# rel-regs.net
KiCad netlist of a schematic drawn in EAGLE
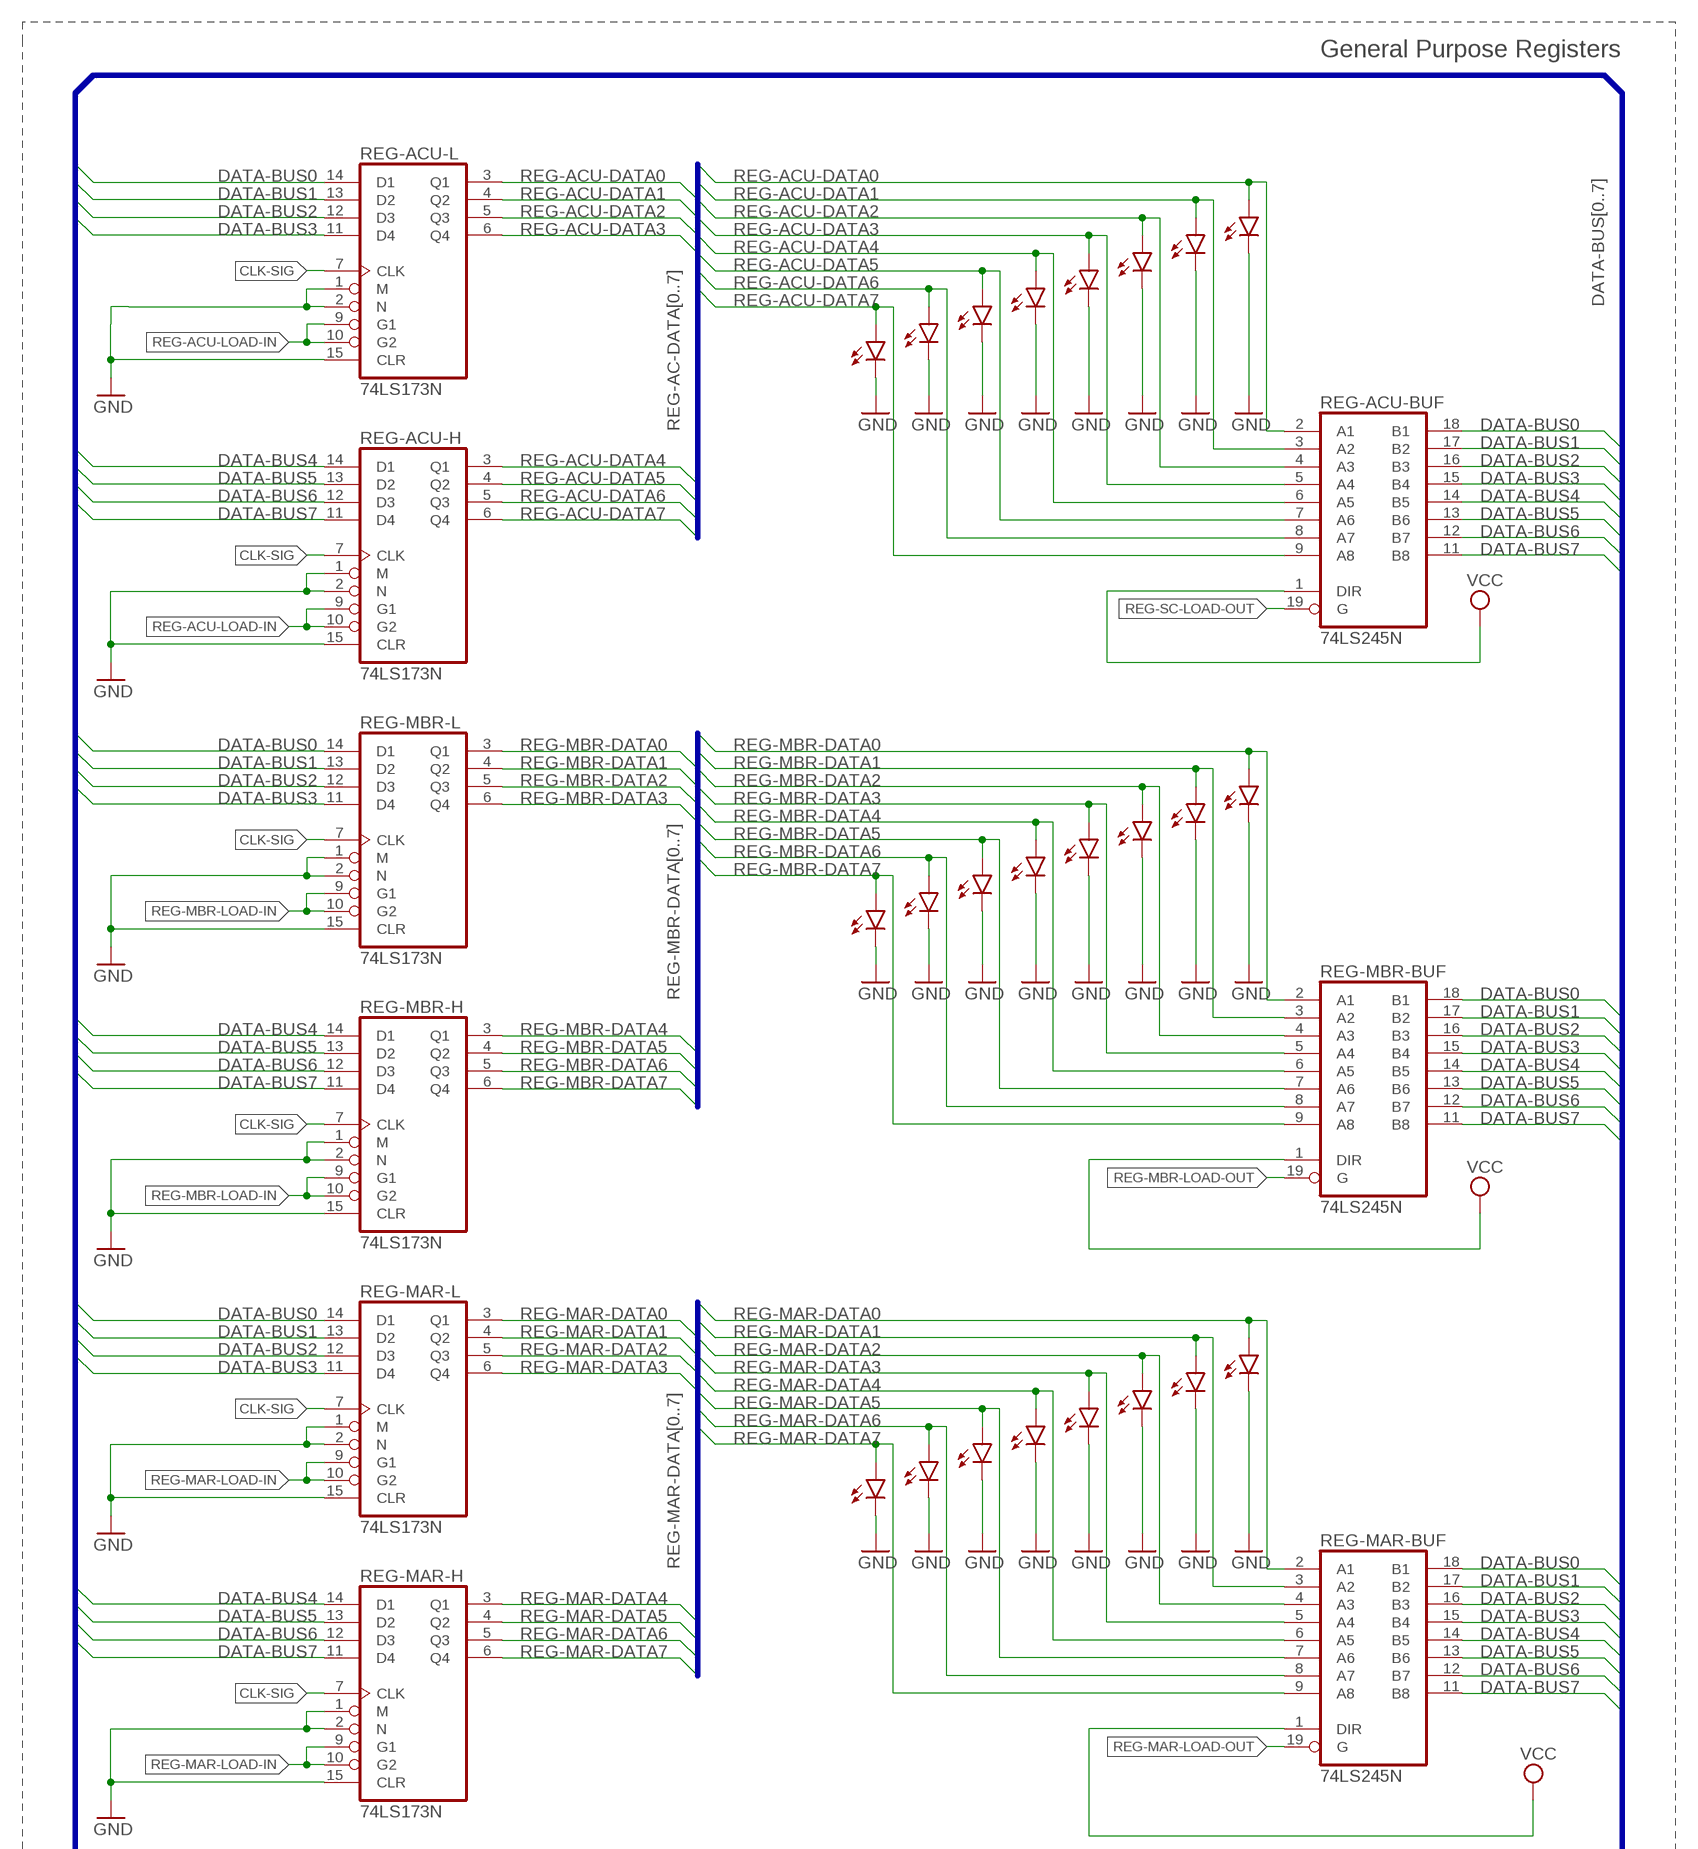
[diagram p0: schematic, sheet 1, part 1 of 2]
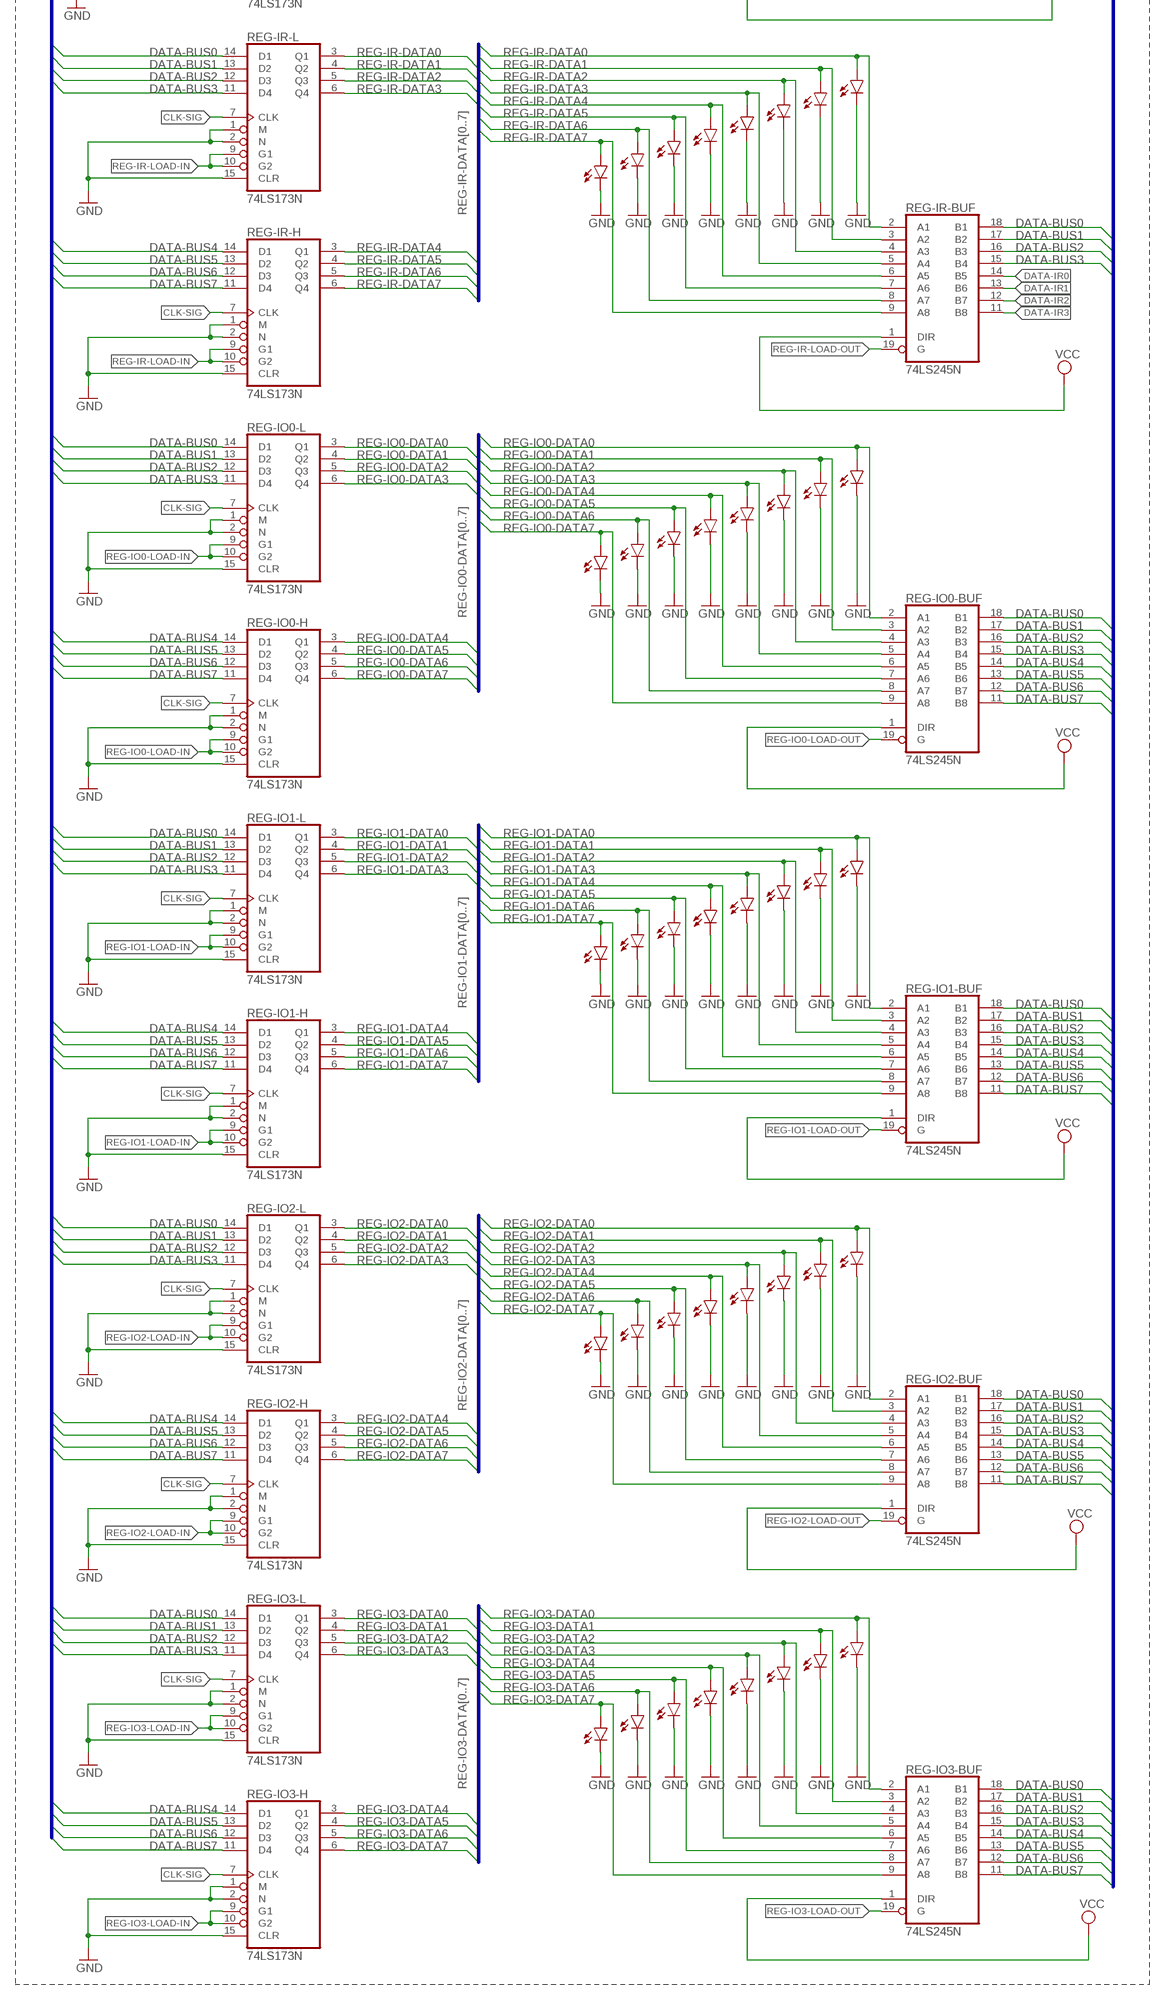
[diagram p1: schematic, sheet 1, part 2 of 2]

(export (version "E")
  (design (tool "Eeschema 10.0.6"))
  (components
    (comp (ref "LED0")
      (value "LED5MM")
      (footprint "eagle-import:LED5MM")
      (libsource (lib "eagle-import") (part "LED5MM"))
    )
    (comp (ref "LED1")
      (value "LED5MM")
      (footprint "eagle-import:LED5MM")
      (libsource (lib "eagle-import") (part "LED5MM"))
    )
    (comp (ref "LED2")
      (value "LED5MM")
      (footprint "eagle-import:LED5MM")
      (libsource (lib "eagle-import") (part "LED5MM"))
    )
    (comp (ref "LED3")
      (value "LED5MM")
      (footprint "eagle-import:LED5MM")
      (libsource (lib "eagle-import") (part "LED5MM"))
    )
    (comp (ref "LED4")
      (value "LED5MM")
      (footprint "eagle-import:LED5MM")
      (libsource (lib "eagle-import") (part "LED5MM"))
    )
    (comp (ref "LED5")
      (value "LED5MM")
      (footprint "eagle-import:LED5MM")
      (libsource (lib "eagle-import") (part "LED5MM"))
    )
    (comp (ref "LED6")
      (value "LED5MM")
      (footprint "eagle-import:LED5MM")
      (libsource (lib "eagle-import") (part "LED5MM"))
    )
    (comp (ref "LED7")
      (value "LED5MM")
      (footprint "eagle-import:LED5MM")
      (libsource (lib "eagle-import") (part "LED5MM"))
    )
    (comp (ref "LED8")
      (value "LED5MM")
      (footprint "eagle-import:LED5MM")
      (libsource (lib "eagle-import") (part "LED5MM"))
    )
    (comp (ref "LED9")
      (value "LED5MM")
      (footprint "eagle-import:LED5MM")
      (libsource (lib "eagle-import") (part "LED5MM"))
    )
    (comp (ref "LED10")
      (value "LED5MM")
      (footprint "eagle-import:LED5MM")
      (libsource (lib "eagle-import") (part "LED5MM"))
    )
    (comp (ref "LED11")
      (value "LED5MM")
      (footprint "eagle-import:LED5MM")
      (libsource (lib "eagle-import") (part "LED5MM"))
    )
    (comp (ref "LED12")
      (value "LED5MM")
      (footprint "eagle-import:LED5MM")
      (libsource (lib "eagle-import") (part "LED5MM"))
    )
    (comp (ref "LED13")
      (value "LED5MM")
      (footprint "eagle-import:LED5MM")
      (libsource (lib "eagle-import") (part "LED5MM"))
    )
    (comp (ref "LED14")
      (value "LED5MM")
      (footprint "eagle-import:LED5MM")
      (libsource (lib "eagle-import") (part "LED5MM"))
    )
    (comp (ref "LED15")
      (value "LED5MM")
      (footprint "eagle-import:LED5MM")
      (libsource (lib "eagle-import") (part "LED5MM"))
    )
    (comp (ref "LED16")
      (value "LED5MM")
      (footprint "eagle-import:LED5MM")
      (libsource (lib "eagle-import") (part "LED5MM"))
    )
    (comp (ref "LED17")
      (value "LED5MM")
      (footprint "eagle-import:LED5MM")
      (libsource (lib "eagle-import") (part "LED5MM"))
    )
    (comp (ref "LED18")
      (value "LED5MM")
      (footprint "eagle-import:LED5MM")
      (libsource (lib "eagle-import") (part "LED5MM"))
    )
    (comp (ref "LED19")
      (value "LED5MM")
      (footprint "eagle-import:LED5MM")
      (libsource (lib "eagle-import") (part "LED5MM"))
    )
    (comp (ref "LED20")
      (value "LED5MM")
      (footprint "eagle-import:LED5MM")
      (libsource (lib "eagle-import") (part "LED5MM"))
    )
    (comp (ref "LED21")
      (value "LED5MM")
      (footprint "eagle-import:LED5MM")
      (libsource (lib "eagle-import") (part "LED5MM"))
    )
    (comp (ref "LED22")
      (value "LED5MM")
      (footprint "eagle-import:LED5MM")
      (libsource (lib "eagle-import") (part "LED5MM"))
    )
    (comp (ref "LED23")
      (value "LED5MM")
      (footprint "eagle-import:LED5MM")
      (libsource (lib "eagle-import") (part "LED5MM"))
    )
    (comp (ref "LED24")
      (value "LED5MM")
      (footprint "eagle-import:LED5MM")
      (libsource (lib "eagle-import") (part "LED5MM"))
    )
    (comp (ref "LED25")
      (value "LED5MM")
      (footprint "eagle-import:LED5MM")
      (libsource (lib "eagle-import") (part "LED5MM"))
    )
    (comp (ref "LED26")
      (value "LED5MM")
      (footprint "eagle-import:LED5MM")
      (libsource (lib "eagle-import") (part "LED5MM"))
    )
    (comp (ref "LED27")
      (value "LED5MM")
      (footprint "eagle-import:LED5MM")
      (libsource (lib "eagle-import") (part "LED5MM"))
    )
    (comp (ref "LED28")
      (value "LED5MM")
      (footprint "eagle-import:LED5MM")
      (libsource (lib "eagle-import") (part "LED5MM"))
    )
    (comp (ref "LED29")
      (value "LED5MM")
      (footprint "eagle-import:LED5MM")
      (libsource (lib "eagle-import") (part "LED5MM"))
    )
    (comp (ref "LED30")
      (value "LED5MM")
      (footprint "eagle-import:LED5MM")
      (libsource (lib "eagle-import") (part "LED5MM"))
    )
    (comp (ref "LED31")
      (value "LED5MM")
      (footprint "eagle-import:LED5MM")
      (libsource (lib "eagle-import") (part "LED5MM"))
    )
    (comp (ref "LED32")
      (value "LED5MM")
      (footprint "eagle-import:LED5MM")
      (libsource (lib "eagle-import") (part "LED5MM"))
    )
    (comp (ref "LED33")
      (value "LED5MM")
      (footprint "eagle-import:LED5MM")
      (libsource (lib "eagle-import") (part "LED5MM"))
    )
    (comp (ref "LED34")
      (value "LED5MM")
      (footprint "eagle-import:LED5MM")
      (libsource (lib "eagle-import") (part "LED5MM"))
    )
    (comp (ref "LED35")
      (value "LED5MM")
      (footprint "eagle-import:LED5MM")
      (libsource (lib "eagle-import") (part "LED5MM"))
    )
    (comp (ref "LED36")
      (value "LED5MM")
      (footprint "eagle-import:LED5MM")
      (libsource (lib "eagle-import") (part "LED5MM"))
    )
    (comp (ref "LED37")
      (value "LED5MM")
      (footprint "eagle-import:LED5MM")
      (libsource (lib "eagle-import") (part "LED5MM"))
    )
    (comp (ref "LED38")
      (value "LED5MM")
      (footprint "eagle-import:LED5MM")
      (libsource (lib "eagle-import") (part "LED5MM"))
    )
    (comp (ref "LED39")
      (value "LED5MM")
      (footprint "eagle-import:LED5MM")
      (libsource (lib "eagle-import") (part "LED5MM"))
    )
    (comp (ref "LED40")
      (value "LED5MM")
      (footprint "eagle-import:LED5MM")
      (libsource (lib "eagle-import") (part "LED5MM"))
    )
    (comp (ref "LED41")
      (value "LED5MM")
      (footprint "eagle-import:LED5MM")
      (libsource (lib "eagle-import") (part "LED5MM"))
    )
    (comp (ref "LED42")
      (value "LED5MM")
      (footprint "eagle-import:LED5MM")
      (libsource (lib "eagle-import") (part "LED5MM"))
    )
    (comp (ref "LED43")
      (value "LED5MM")
      (footprint "eagle-import:LED5MM")
      (libsource (lib "eagle-import") (part "LED5MM"))
    )
    (comp (ref "LED44")
      (value "LED5MM")
      (footprint "eagle-import:LED5MM")
      (libsource (lib "eagle-import") (part "LED5MM"))
    )
    (comp (ref "LED45")
      (value "LED5MM")
      (footprint "eagle-import:LED5MM")
      (libsource (lib "eagle-import") (part "LED5MM"))
    )
    (comp (ref "LED46")
      (value "LED5MM")
      (footprint "eagle-import:LED5MM")
      (libsource (lib "eagle-import") (part "LED5MM"))
    )
    (comp (ref "LED47")
      (value "LED5MM")
      (footprint "eagle-import:LED5MM")
      (libsource (lib "eagle-import") (part "LED5MM"))
    )
    (comp (ref "LED48")
      (value "LED5MM")
      (footprint "eagle-import:LED5MM")
      (libsource (lib "eagle-import") (part "LED5MM"))
    )
    (comp (ref "LED49")
      (value "LED5MM")
      (footprint "eagle-import:LED5MM")
      (libsource (lib "eagle-import") (part "LED5MM"))
    )
    (comp (ref "LED50")
      (value "LED5MM")
      (footprint "eagle-import:LED5MM")
      (libsource (lib "eagle-import") (part "LED5MM"))
    )
    (comp (ref "LED51")
      (value "LED5MM")
      (footprint "eagle-import:LED5MM")
      (libsource (lib "eagle-import") (part "LED5MM"))
    )
    (comp (ref "LED52")
      (value "LED5MM")
      (footprint "eagle-import:LED5MM")
      (libsource (lib "eagle-import") (part "LED5MM"))
    )
    (comp (ref "LED53")
      (value "LED5MM")
      (footprint "eagle-import:LED5MM")
      (libsource (lib "eagle-import") (part "LED5MM"))
    )
    (comp (ref "LED54")
      (value "LED5MM")
      (footprint "eagle-import:LED5MM")
      (libsource (lib "eagle-import") (part "LED5MM"))
    )
    (comp (ref "LED55")
      (value "LED5MM")
      (footprint "eagle-import:LED5MM")
      (libsource (lib "eagle-import") (part "LED5MM"))
    )
    (comp (ref "LED56")
      (value "LED5MM")
      (footprint "eagle-import:LED5MM")
      (libsource (lib "eagle-import") (part "LED5MM"))
    )
    (comp (ref "LED57")
      (value "LED5MM")
      (footprint "eagle-import:LED5MM")
      (libsource (lib "eagle-import") (part "LED5MM"))
    )
    (comp (ref "LED58")
      (value "LED5MM")
      (footprint "eagle-import:LED5MM")
      (libsource (lib "eagle-import") (part "LED5MM"))
    )
    (comp (ref "LED59")
      (value "LED5MM")
      (footprint "eagle-import:LED5MM")
      (libsource (lib "eagle-import") (part "LED5MM"))
    )
    (comp (ref "LED60")
      (value "LED5MM")
      (footprint "eagle-import:LED5MM")
      (libsource (lib "eagle-import") (part "LED5MM"))
    )
    (comp (ref "LED61")
      (value "LED5MM")
      (footprint "eagle-import:LED5MM")
      (libsource (lib "eagle-import") (part "LED5MM"))
    )
    (comp (ref "LED62")
      (value "LED5MM")
      (footprint "eagle-import:LED5MM")
      (libsource (lib "eagle-import") (part "LED5MM"))
    )
    (comp (ref "LED63")
      (value "LED5MM")
      (footprint "eagle-import:LED5MM")
      (libsource (lib "eagle-import") (part "LED5MM"))
    )
    (comp (ref "REG-ACU-BUF")
      (value "74LS245N")
      (footprint "eagle-import:DIL20")
      (libsource (lib "eagle-import") (part "74245NLS"))
    )
    (comp (ref "REG-ACU-H")
      (value "74LS173N")
      (footprint "eagle-import:DIL16")
      (libsource (lib "eagle-import") (part "74173NLS"))
    )
    (comp (ref "REG-ACU-L")
      (value "74LS173N")
      (footprint "eagle-import:DIL16")
      (libsource (lib "eagle-import") (part "74173NLS"))
    )
    (comp (ref "REG-IO0-BUF")
      (value "74LS245N")
      (footprint "eagle-import:DIL20")
      (libsource (lib "eagle-import") (part "74245NLS"))
    )
    (comp (ref "REG-IO0-H")
      (value "74LS173N")
      (footprint "eagle-import:DIL16")
      (libsource (lib "eagle-import") (part "74173NLS"))
    )
    (comp (ref "REG-IO0-L")
      (value "74LS173N")
      (footprint "eagle-import:DIL16")
      (libsource (lib "eagle-import") (part "74173NLS"))
    )
    (comp (ref "REG-IO1-BUF")
      (value "74LS245N")
      (footprint "eagle-import:DIL20")
      (libsource (lib "eagle-import") (part "74245NLS"))
    )
    (comp (ref "REG-IO1-H")
      (value "74LS173N")
      (footprint "eagle-import:DIL16")
      (libsource (lib "eagle-import") (part "74173NLS"))
    )
    (comp (ref "REG-IO1-L")
      (value "74LS173N")
      (footprint "eagle-import:DIL16")
      (libsource (lib "eagle-import") (part "74173NLS"))
    )
    (comp (ref "REG-IO2-BUF")
      (value "74LS245N")
      (footprint "eagle-import:DIL20")
      (libsource (lib "eagle-import") (part "74245NLS"))
    )
    (comp (ref "REG-IO2-H")
      (value "74LS173N")
      (footprint "eagle-import:DIL16")
      (libsource (lib "eagle-import") (part "74173NLS"))
    )
    (comp (ref "REG-IO2-L")
      (value "74LS173N")
      (footprint "eagle-import:DIL16")
      (libsource (lib "eagle-import") (part "74173NLS"))
    )
    (comp (ref "REG-IO3-BUF")
      (value "74LS245N")
      (footprint "eagle-import:DIL20")
      (libsource (lib "eagle-import") (part "74245NLS"))
    )
    (comp (ref "REG-IO3-H")
      (value "74LS173N")
      (footprint "eagle-import:DIL16")
      (libsource (lib "eagle-import") (part "74173NLS"))
    )
    (comp (ref "REG-IO3-L")
      (value "74LS173N")
      (footprint "eagle-import:DIL16")
      (libsource (lib "eagle-import") (part "74173NLS"))
    )
    (comp (ref "REG-IR-BUF")
      (value "74LS245N")
      (footprint "eagle-import:DIL20")
      (libsource (lib "eagle-import") (part "74245NLS"))
    )
    (comp (ref "REG-IR-H")
      (value "74LS173N")
      (footprint "eagle-import:DIL16")
      (libsource (lib "eagle-import") (part "74173NLS"))
    )
    (comp (ref "REG-IR-L")
      (value "74LS173N")
      (footprint "eagle-import:DIL16")
      (libsource (lib "eagle-import") (part "74173NLS"))
    )
    (comp (ref "REG-MAR-BUF")
      (value "74LS245N")
      (footprint "eagle-import:DIL20")
      (libsource (lib "eagle-import") (part "74245NLS"))
    )
    (comp (ref "REG-MAR-H")
      (value "74LS173N")
      (footprint "eagle-import:DIL16")
      (libsource (lib "eagle-import") (part "74173NLS"))
    )
    (comp (ref "REG-MAR-L")
      (value "74LS173N")
      (footprint "eagle-import:DIL16")
      (libsource (lib "eagle-import") (part "74173NLS"))
    )
    (comp (ref "REG-MBR-BUF")
      (value "74LS245N")
      (footprint "eagle-import:DIL20")
      (libsource (lib "eagle-import") (part "74245NLS"))
    )
    (comp (ref "REG-MBR-H")
      (value "74LS173N")
      (footprint "eagle-import:DIL16")
      (libsource (lib "eagle-import") (part "74173NLS"))
    )
    (comp (ref "REG-MBR-L")
      (value "74LS173N")
      (footprint "eagle-import:DIL16")
      (libsource (lib "eagle-import") (part "74173NLS"))
    )
  )
  (nets
    (net (code "9") (name "/DATA-BUS0") (class "Default")
      (node (ref "REG-ACU-BUF") (pin "18") (pinfunction "B1_18") (pintype "bidirectional"))
      (node (ref "REG-ACU-L") (pin "14") (pinfunction "D1_14") (pintype "input"))
      (node (ref "REG-IO0-BUF") (pin "18") (pinfunction "B1_18") (pintype "bidirectional"))
      (node (ref "REG-IO0-L") (pin "14") (pinfunction "D1_14") (pintype "input"))
      (node (ref "REG-IO1-BUF") (pin "18") (pinfunction "B1_18") (pintype "bidirectional"))
      (node (ref "REG-IO1-L") (pin "14") (pinfunction "D1_14") (pintype "input"))
      (node (ref "REG-IO2-BUF") (pin "18") (pinfunction "B1_18") (pintype "bidirectional"))
      (node (ref "REG-IO2-L") (pin "14") (pinfunction "D1_14") (pintype "input"))
      (node (ref "REG-IO3-BUF") (pin "18") (pinfunction "B1_18") (pintype "bidirectional"))
      (node (ref "REG-IO3-L") (pin "14") (pinfunction "D1_14") (pintype "input"))
      (node (ref "REG-IR-BUF") (pin "18") (pinfunction "B1_18") (pintype "bidirectional"))
      (node (ref "REG-IR-L") (pin "14") (pinfunction "D1_14") (pintype "input"))
      (node (ref "REG-MAR-BUF") (pin "18") (pinfunction "B1_18") (pintype "bidirectional"))
      (node (ref "REG-MAR-L") (pin "14") (pinfunction "D1_14") (pintype "input"))
      (node (ref "REG-MBR-BUF") (pin "18") (pinfunction "B1_18") (pintype "bidirectional"))
      (node (ref "REG-MBR-L") (pin "14") (pinfunction "D1_14") (pintype "input"))
    )
    (net (code "10") (name "/DATA-BUS1") (class "Default")
      (node (ref "REG-ACU-BUF") (pin "17") (pinfunction "B2_17") (pintype "bidirectional"))
      (node (ref "REG-ACU-L") (pin "13") (pinfunction "D2_13") (pintype "input"))
      (node (ref "REG-IO0-BUF") (pin "17") (pinfunction "B2_17") (pintype "bidirectional"))
      (node (ref "REG-IO0-L") (pin "13") (pinfunction "D2_13") (pintype "input"))
      (node (ref "REG-IO1-BUF") (pin "17") (pinfunction "B2_17") (pintype "bidirectional"))
      (node (ref "REG-IO1-L") (pin "13") (pinfunction "D2_13") (pintype "input"))
      (node (ref "REG-IO2-BUF") (pin "17") (pinfunction "B2_17") (pintype "bidirectional"))
      (node (ref "REG-IO2-L") (pin "13") (pinfunction "D2_13") (pintype "input"))
      (node (ref "REG-IO3-BUF") (pin "17") (pinfunction "B2_17") (pintype "bidirectional"))
      (node (ref "REG-IO3-L") (pin "13") (pinfunction "D2_13") (pintype "input"))
      (node (ref "REG-IR-BUF") (pin "17") (pinfunction "B2_17") (pintype "bidirectional"))
      (node (ref "REG-IR-L") (pin "13") (pinfunction "D2_13") (pintype "input"))
      (node (ref "REG-MAR-BUF") (pin "17") (pinfunction "B2_17") (pintype "bidirectional"))
      (node (ref "REG-MAR-L") (pin "13") (pinfunction "D2_13") (pintype "input"))
      (node (ref "REG-MBR-BUF") (pin "17") (pinfunction "B2_17") (pintype "bidirectional"))
      (node (ref "REG-MBR-L") (pin "13") (pinfunction "D2_13") (pintype "input"))
    )
    (net (code "11") (name "/DATA-BUS2") (class "Default")
      (node (ref "REG-ACU-BUF") (pin "16") (pinfunction "B3_16") (pintype "bidirectional"))
      (node (ref "REG-ACU-L") (pin "12") (pinfunction "D3_12") (pintype "input"))
      (node (ref "REG-IO0-BUF") (pin "16") (pinfunction "B3_16") (pintype "bidirectional"))
      (node (ref "REG-IO0-L") (pin "12") (pinfunction "D3_12") (pintype "input"))
      (node (ref "REG-IO1-BUF") (pin "16") (pinfunction "B3_16") (pintype "bidirectional"))
      (node (ref "REG-IO1-L") (pin "12") (pinfunction "D3_12") (pintype "input"))
      (node (ref "REG-IO2-BUF") (pin "16") (pinfunction "B3_16") (pintype "bidirectional"))
      (node (ref "REG-IO2-L") (pin "12") (pinfunction "D3_12") (pintype "input"))
      (node (ref "REG-IO3-BUF") (pin "16") (pinfunction "B3_16") (pintype "bidirectional"))
      (node (ref "REG-IO3-L") (pin "12") (pinfunction "D3_12") (pintype "input"))
      (node (ref "REG-IR-BUF") (pin "16") (pinfunction "B3_16") (pintype "bidirectional"))
      (node (ref "REG-IR-L") (pin "12") (pinfunction "D3_12") (pintype "input"))
      (node (ref "REG-MAR-BUF") (pin "16") (pinfunction "B3_16") (pintype "bidirectional"))
      (node (ref "REG-MAR-L") (pin "12") (pinfunction "D3_12") (pintype "input"))
      (node (ref "REG-MBR-BUF") (pin "16") (pinfunction "B3_16") (pintype "bidirectional"))
      (node (ref "REG-MBR-L") (pin "12") (pinfunction "D3_12") (pintype "input"))
    )
    (net (code "12") (name "/DATA-BUS3") (class "Default")
      (node (ref "REG-ACU-BUF") (pin "15") (pinfunction "B4_15") (pintype "bidirectional"))
      (node (ref "REG-ACU-L") (pin "11") (pinfunction "D4_11") (pintype "input"))
      (node (ref "REG-IO0-BUF") (pin "15") (pinfunction "B4_15") (pintype "bidirectional"))
      (node (ref "REG-IO0-L") (pin "11") (pinfunction "D4_11") (pintype "input"))
      (node (ref "REG-IO1-BUF") (pin "15") (pinfunction "B4_15") (pintype "bidirectional"))
      (node (ref "REG-IO1-L") (pin "11") (pinfunction "D4_11") (pintype "input"))
      (node (ref "REG-IO2-BUF") (pin "15") (pinfunction "B4_15") (pintype "bidirectional"))
      (node (ref "REG-IO2-L") (pin "11") (pinfunction "D4_11") (pintype "input"))
      (node (ref "REG-IO3-BUF") (pin "15") (pinfunction "B4_15") (pintype "bidirectional"))
      (node (ref "REG-IO3-L") (pin "11") (pinfunction "D4_11") (pintype "input"))
      (node (ref "REG-IR-BUF") (pin "15") (pinfunction "B4_15") (pintype "bidirectional"))
      (node (ref "REG-IR-L") (pin "11") (pinfunction "D4_11") (pintype "input"))
      (node (ref "REG-MAR-BUF") (pin "15") (pinfunction "B4_15") (pintype "bidirectional"))
      (node (ref "REG-MAR-L") (pin "11") (pinfunction "D4_11") (pintype "input"))
      (node (ref "REG-MBR-BUF") (pin "15") (pinfunction "B4_15") (pintype "bidirectional"))
      (node (ref "REG-MBR-L") (pin "11") (pinfunction "D4_11") (pintype "input"))
    )
    (net (code "13") (name "/DATA-BUS4") (class "Default")
      (node (ref "REG-ACU-BUF") (pin "14") (pinfunction "B5_14") (pintype "bidirectional"))
      (node (ref "REG-ACU-H") (pin "14") (pinfunction "D1_14") (pintype "input"))
      (node (ref "REG-IO0-BUF") (pin "14") (pinfunction "B5_14") (pintype "bidirectional"))
      (node (ref "REG-IO0-H") (pin "14") (pinfunction "D1_14") (pintype "input"))
      (node (ref "REG-IO1-BUF") (pin "14") (pinfunction "B5_14") (pintype "bidirectional"))
      (node (ref "REG-IO1-H") (pin "14") (pinfunction "D1_14") (pintype "input"))
      (node (ref "REG-IO2-BUF") (pin "14") (pinfunction "B5_14") (pintype "bidirectional"))
      (node (ref "REG-IO2-H") (pin "14") (pinfunction "D1_14") (pintype "input"))
      (node (ref "REG-IO3-BUF") (pin "14") (pinfunction "B5_14") (pintype "bidirectional"))
      (node (ref "REG-IO3-H") (pin "14") (pinfunction "D1_14") (pintype "input"))
      (node (ref "REG-IR-H") (pin "14") (pinfunction "D1_14") (pintype "input"))
      (node (ref "REG-MAR-BUF") (pin "14") (pinfunction "B5_14") (pintype "bidirectional"))
      (node (ref "REG-MAR-H") (pin "14") (pinfunction "D1_14") (pintype "input"))
      (node (ref "REG-MBR-BUF") (pin "14") (pinfunction "B5_14") (pintype "bidirectional"))
      (node (ref "REG-MBR-H") (pin "14") (pinfunction "D1_14") (pintype "input"))
    )
    (net (code "14") (name "/DATA-BUS5") (class "Default")
      (node (ref "REG-ACU-BUF") (pin "13") (pinfunction "B6_13") (pintype "bidirectional"))
      (node (ref "REG-ACU-H") (pin "13") (pinfunction "D2_13") (pintype "input"))
      (node (ref "REG-IO0-BUF") (pin "13") (pinfunction "B6_13") (pintype "bidirectional"))
      (node (ref "REG-IO0-H") (pin "13") (pinfunction "D2_13") (pintype "input"))
      (node (ref "REG-IO1-BUF") (pin "13") (pinfunction "B6_13") (pintype "bidirectional"))
      (node (ref "REG-IO1-H") (pin "13") (pinfunction "D2_13") (pintype "input"))
      (node (ref "REG-IO2-BUF") (pin "13") (pinfunction "B6_13") (pintype "bidirectional"))
      (node (ref "REG-IO2-H") (pin "13") (pinfunction "D2_13") (pintype "input"))
      (node (ref "REG-IO3-BUF") (pin "13") (pinfunction "B6_13") (pintype "bidirectional"))
      (node (ref "REG-IO3-H") (pin "13") (pinfunction "D2_13") (pintype "input"))
      (node (ref "REG-IR-H") (pin "13") (pinfunction "D2_13") (pintype "input"))
      (node (ref "REG-MAR-BUF") (pin "13") (pinfunction "B6_13") (pintype "bidirectional"))
      (node (ref "REG-MAR-H") (pin "13") (pinfunction "D2_13") (pintype "input"))
      (node (ref "REG-MBR-BUF") (pin "13") (pinfunction "B6_13") (pintype "bidirectional"))
      (node (ref "REG-MBR-H") (pin "13") (pinfunction "D2_13") (pintype "input"))
    )
    (net (code "15") (name "/DATA-BUS6") (class "Default")
      (node (ref "REG-ACU-BUF") (pin "12") (pinfunction "B7_12") (pintype "bidirectional"))
      (node (ref "REG-ACU-H") (pin "12") (pinfunction "D3_12") (pintype "input"))
      (node (ref "REG-IO0-BUF") (pin "12") (pinfunction "B7_12") (pintype "bidirectional"))
      (node (ref "REG-IO0-H") (pin "12") (pinfunction "D3_12") (pintype "input"))
      (node (ref "REG-IO1-BUF") (pin "12") (pinfunction "B7_12") (pintype "bidirectional"))
      (node (ref "REG-IO1-H") (pin "12") (pinfunction "D3_12") (pintype "input"))
      (node (ref "REG-IO2-BUF") (pin "12") (pinfunction "B7_12") (pintype "bidirectional"))
      (node (ref "REG-IO2-H") (pin "12") (pinfunction "D3_12") (pintype "input"))
      (node (ref "REG-IO3-BUF") (pin "12") (pinfunction "B7_12") (pintype "bidirectional"))
      (node (ref "REG-IO3-H") (pin "12") (pinfunction "D3_12") (pintype "input"))
      (node (ref "REG-IR-H") (pin "12") (pinfunction "D3_12") (pintype "input"))
      (node (ref "REG-MAR-BUF") (pin "12") (pinfunction "B7_12") (pintype "bidirectional"))
      (node (ref "REG-MAR-H") (pin "12") (pinfunction "D3_12") (pintype "input"))
      (node (ref "REG-MBR-BUF") (pin "12") (pinfunction "B7_12") (pintype "bidirectional"))
      (node (ref "REG-MBR-H") (pin "12") (pinfunction "D3_12") (pintype "input"))
    )
    (net (code "16") (name "/DATA-BUS7") (class "Default")
      (node (ref "REG-ACU-BUF") (pin "11") (pinfunction "B8_11") (pintype "bidirectional"))
      (node (ref "REG-ACU-H") (pin "11") (pinfunction "D4_11") (pintype "input"))
      (node (ref "REG-IO0-BUF") (pin "11") (pinfunction "B8_11") (pintype "bidirectional"))
      (node (ref "REG-IO0-H") (pin "11") (pinfunction "D4_11") (pintype "input"))
      (node (ref "REG-IO1-BUF") (pin "11") (pinfunction "B8_11") (pintype "bidirectional"))
      (node (ref "REG-IO1-H") (pin "11") (pinfunction "D4_11") (pintype "input"))
      (node (ref "REG-IO2-BUF") (pin "11") (pinfunction "B8_11") (pintype "bidirectional"))
      (node (ref "REG-IO2-H") (pin "11") (pinfunction "D4_11") (pintype "input"))
      (node (ref "REG-IO3-BUF") (pin "11") (pinfunction "B8_11") (pintype "bidirectional"))
      (node (ref "REG-IO3-H") (pin "11") (pinfunction "D4_11") (pintype "input"))
      (node (ref "REG-IR-H") (pin "11") (pinfunction "D4_11") (pintype "input"))
      (node (ref "REG-MAR-BUF") (pin "11") (pinfunction "B8_11") (pintype "bidirectional"))
      (node (ref "REG-MAR-H") (pin "11") (pinfunction "D4_11") (pintype "input"))
      (node (ref "REG-MBR-BUF") (pin "11") (pinfunction "B8_11") (pintype "bidirectional"))
      (node (ref "REG-MBR-H") (pin "11") (pinfunction "D4_11") (pintype "input"))
    )
    (net (code "19") (name "/REG-ACU-DATA0") (class "Default")
      (node (ref "LED0") (pin "A") (pinfunction "A_A") (pintype "passive"))
      (node (ref "REG-ACU-BUF") (pin "2") (pinfunction "A1_2") (pintype "bidirectional"))
      (node (ref "REG-ACU-L") (pin "3") (pinfunction "Q1_3") (pintype "tri_state"))
    )
    (net (code "20") (name "/REG-ACU-DATA1") (class "Default")
      (node (ref "LED1") (pin "A") (pinfunction "A_A") (pintype "passive"))
      (node (ref "REG-ACU-BUF") (pin "3") (pinfunction "A2_3") (pintype "bidirectional"))
      (node (ref "REG-ACU-L") (pin "4") (pinfunction "Q2_4") (pintype "tri_state"))
    )
    (net (code "21") (name "/REG-ACU-DATA2") (class "Default")
      (node (ref "LED2") (pin "A") (pinfunction "A_A") (pintype "passive"))
      (node (ref "REG-ACU-BUF") (pin "4") (pinfunction "A3_4") (pintype "bidirectional"))
      (node (ref "REG-ACU-L") (pin "5") (pinfunction "Q3_5") (pintype "tri_state"))
    )
    (net (code "22") (name "/REG-ACU-DATA3") (class "Default")
      (node (ref "LED3") (pin "A") (pinfunction "A_A") (pintype "passive"))
      (node (ref "REG-ACU-BUF") (pin "5") (pinfunction "A4_5") (pintype "bidirectional"))
      (node (ref "REG-ACU-L") (pin "6") (pinfunction "Q4_6") (pintype "tri_state"))
    )
    (net (code "23") (name "/REG-ACU-DATA4") (class "Default")
      (node (ref "LED4") (pin "A") (pinfunction "A_A") (pintype "passive"))
      (node (ref "REG-ACU-BUF") (pin "6") (pinfunction "A5_6") (pintype "bidirectional"))
      (node (ref "REG-ACU-H") (pin "3") (pinfunction "Q1_3") (pintype "tri_state"))
    )
    (net (code "24") (name "/REG-ACU-DATA5") (class "Default")
      (node (ref "LED5") (pin "A") (pinfunction "A_A") (pintype "passive"))
      (node (ref "REG-ACU-BUF") (pin "7") (pinfunction "A6_7") (pintype "bidirectional"))
      (node (ref "REG-ACU-H") (pin "4") (pinfunction "Q2_4") (pintype "tri_state"))
    )
    (net (code "25") (name "/REG-ACU-DATA6") (class "Default")
      (node (ref "LED6") (pin "A") (pinfunction "A_A") (pintype "passive"))
      (node (ref "REG-ACU-BUF") (pin "8") (pinfunction "A7_8") (pintype "bidirectional"))
      (node (ref "REG-ACU-H") (pin "5") (pinfunction "Q3_5") (pintype "tri_state"))
    )
    (net (code "26") (name "/REG-ACU-DATA7") (class "Default")
      (node (ref "LED7") (pin "A") (pinfunction "A_A") (pintype "passive"))
      (node (ref "REG-ACU-BUF") (pin "9") (pinfunction "A8_9") (pintype "bidirectional"))
      (node (ref "REG-ACU-H") (pin "6") (pinfunction "Q4_6") (pintype "tri_state"))
    )
    (net (code "27") (name "/REG-IO0-DATA0") (class "Default")
      (node (ref "LED32") (pin "A") (pinfunction "A_A") (pintype "passive"))
      (node (ref "REG-IO0-BUF") (pin "2") (pinfunction "A1_2") (pintype "bidirectional"))
      (node (ref "REG-IO0-L") (pin "3") (pinfunction "Q1_3") (pintype "tri_state"))
    )
    (net (code "28") (name "/REG-IO0-DATA1") (class "Default")
      (node (ref "LED33") (pin "A") (pinfunction "A_A") (pintype "passive"))
      (node (ref "REG-IO0-BUF") (pin "3") (pinfunction "A2_3") (pintype "bidirectional"))
      (node (ref "REG-IO0-L") (pin "4") (pinfunction "Q2_4") (pintype "tri_state"))
    )
    (net (code "29") (name "/REG-IO0-DATA2") (class "Default")
      (node (ref "LED34") (pin "A") (pinfunction "A_A") (pintype "passive"))
      (node (ref "REG-IO0-BUF") (pin "4") (pinfunction "A3_4") (pintype "bidirectional"))
      (node (ref "REG-IO0-L") (pin "5") (pinfunction "Q3_5") (pintype "tri_state"))
    )
    (net (code "30") (name "/REG-IO0-DATA3") (class "Default")
      (node (ref "LED35") (pin "A") (pinfunction "A_A") (pintype "passive"))
      (node (ref "REG-IO0-BUF") (pin "5") (pinfunction "A4_5") (pintype "bidirectional"))
      (node (ref "REG-IO0-L") (pin "6") (pinfunction "Q4_6") (pintype "tri_state"))
    )
    (net (code "31") (name "/REG-IO0-DATA4") (class "Default")
      (node (ref "LED36") (pin "A") (pinfunction "A_A") (pintype "passive"))
      (node (ref "REG-IO0-BUF") (pin "6") (pinfunction "A5_6") (pintype "bidirectional"))
      (node (ref "REG-IO0-H") (pin "3") (pinfunction "Q1_3") (pintype "tri_state"))
    )
    (net (code "32") (name "/REG-IO0-DATA5") (class "Default")
      (node (ref "LED37") (pin "A") (pinfunction "A_A") (pintype "passive"))
      (node (ref "REG-IO0-BUF") (pin "7") (pinfunction "A6_7") (pintype "bidirectional"))
      (node (ref "REG-IO0-H") (pin "4") (pinfunction "Q2_4") (pintype "tri_state"))
    )
    (net (code "33") (name "/REG-IO0-DATA6") (class "Default")
      (node (ref "LED38") (pin "A") (pinfunction "A_A") (pintype "passive"))
      (node (ref "REG-IO0-BUF") (pin "8") (pinfunction "A7_8") (pintype "bidirectional"))
      (node (ref "REG-IO0-H") (pin "5") (pinfunction "Q3_5") (pintype "tri_state"))
    )
    (net (code "34") (name "/REG-IO0-DATA7") (class "Default")
      (node (ref "LED39") (pin "A") (pinfunction "A_A") (pintype "passive"))
      (node (ref "REG-IO0-BUF") (pin "9") (pinfunction "A8_9") (pintype "bidirectional"))
      (node (ref "REG-IO0-H") (pin "6") (pinfunction "Q4_6") (pintype "tri_state"))
    )
    (net (code "36") (name "/REG-IO1-DATA0") (class "Default")
      (node (ref "LED40") (pin "A") (pinfunction "A_A") (pintype "passive"))
      (node (ref "REG-IO1-BUF") (pin "2") (pinfunction "A1_2") (pintype "bidirectional"))
      (node (ref "REG-IO1-L") (pin "3") (pinfunction "Q1_3") (pintype "tri_state"))
    )
    (net (code "37") (name "/REG-IO1-DATA1") (class "Default")
      (node (ref "LED41") (pin "A") (pinfunction "A_A") (pintype "passive"))
      (node (ref "REG-IO1-BUF") (pin "3") (pinfunction "A2_3") (pintype "bidirectional"))
      (node (ref "REG-IO1-L") (pin "4") (pinfunction "Q2_4") (pintype "tri_state"))
    )
    (net (code "38") (name "/REG-IO1-DATA2") (class "Default")
      (node (ref "LED42") (pin "A") (pinfunction "A_A") (pintype "passive"))
      (node (ref "REG-IO1-BUF") (pin "4") (pinfunction "A3_4") (pintype "bidirectional"))
      (node (ref "REG-IO1-L") (pin "5") (pinfunction "Q3_5") (pintype "tri_state"))
    )
    (net (code "39") (name "/REG-IO1-DATA3") (class "Default")
      (node (ref "LED43") (pin "A") (pinfunction "A_A") (pintype "passive"))
      (node (ref "REG-IO1-BUF") (pin "5") (pinfunction "A4_5") (pintype "bidirectional"))
      (node (ref "REG-IO1-L") (pin "6") (pinfunction "Q4_6") (pintype "tri_state"))
    )
    (net (code "40") (name "/REG-IO1-DATA4") (class "Default")
      (node (ref "LED44") (pin "A") (pinfunction "A_A") (pintype "passive"))
      (node (ref "REG-IO1-BUF") (pin "6") (pinfunction "A5_6") (pintype "bidirectional"))
      (node (ref "REG-IO1-H") (pin "3") (pinfunction "Q1_3") (pintype "tri_state"))
    )
    (net (code "41") (name "/REG-IO1-DATA5") (class "Default")
      (node (ref "LED45") (pin "A") (pinfunction "A_A") (pintype "passive"))
      (node (ref "REG-IO1-BUF") (pin "7") (pinfunction "A6_7") (pintype "bidirectional"))
      (node (ref "REG-IO1-H") (pin "4") (pinfunction "Q2_4") (pintype "tri_state"))
    )
    (net (code "42") (name "/REG-IO1-DATA6") (class "Default")
      (node (ref "LED46") (pin "A") (pinfunction "A_A") (pintype "passive"))
      (node (ref "REG-IO1-BUF") (pin "8") (pinfunction "A7_8") (pintype "bidirectional"))
      (node (ref "REG-IO1-H") (pin "5") (pinfunction "Q3_5") (pintype "tri_state"))
    )
    (net (code "43") (name "/REG-IO1-DATA7") (class "Default")
      (node (ref "LED47") (pin "A") (pinfunction "A_A") (pintype "passive"))
      (node (ref "REG-IO1-BUF") (pin "9") (pinfunction "A8_9") (pintype "bidirectional"))
      (node (ref "REG-IO1-H") (pin "6") (pinfunction "Q4_6") (pintype "tri_state"))
    )
    (net (code "45") (name "/REG-IO2-DATA0") (class "Default")
      (node (ref "LED48") (pin "A") (pinfunction "A_A") (pintype "passive"))
      (node (ref "REG-IO2-BUF") (pin "2") (pinfunction "A1_2") (pintype "bidirectional"))
      (node (ref "REG-IO2-L") (pin "3") (pinfunction "Q1_3") (pintype "tri_state"))
    )
    (net (code "46") (name "/REG-IO2-DATA1") (class "Default")
      (node (ref "LED49") (pin "A") (pinfunction "A_A") (pintype "passive"))
      (node (ref "REG-IO2-BUF") (pin "3") (pinfunction "A2_3") (pintype "bidirectional"))
      (node (ref "REG-IO2-L") (pin "4") (pinfunction "Q2_4") (pintype "tri_state"))
    )
    (net (code "47") (name "/REG-IO2-DATA2") (class "Default")
      (node (ref "LED50") (pin "A") (pinfunction "A_A") (pintype "passive"))
      (node (ref "REG-IO2-BUF") (pin "4") (pinfunction "A3_4") (pintype "bidirectional"))
      (node (ref "REG-IO2-L") (pin "5") (pinfunction "Q3_5") (pintype "tri_state"))
    )
    (net (code "48") (name "/REG-IO2-DATA3") (class "Default")
      (node (ref "LED51") (pin "A") (pinfunction "A_A") (pintype "passive"))
      (node (ref "REG-IO2-BUF") (pin "5") (pinfunction "A4_5") (pintype "bidirectional"))
      (node (ref "REG-IO2-L") (pin "6") (pinfunction "Q4_6") (pintype "tri_state"))
    )
    (net (code "49") (name "/REG-IO2-DATA4") (class "Default")
      (node (ref "LED52") (pin "A") (pinfunction "A_A") (pintype "passive"))
      (node (ref "REG-IO2-BUF") (pin "6") (pinfunction "A5_6") (pintype "bidirectional"))
      (node (ref "REG-IO2-H") (pin "3") (pinfunction "Q1_3") (pintype "tri_state"))
    )
    (net (code "50") (name "/REG-IO2-DATA5") (class "Default")
      (node (ref "LED53") (pin "A") (pinfunction "A_A") (pintype "passive"))
      (node (ref "REG-IO2-BUF") (pin "7") (pinfunction "A6_7") (pintype "bidirectional"))
      (node (ref "REG-IO2-H") (pin "4") (pinfunction "Q2_4") (pintype "tri_state"))
    )
    (net (code "51") (name "/REG-IO2-DATA6") (class "Default")
      (node (ref "LED54") (pin "A") (pinfunction "A_A") (pintype "passive"))
      (node (ref "REG-IO2-BUF") (pin "8") (pinfunction "A7_8") (pintype "bidirectional"))
      (node (ref "REG-IO2-H") (pin "5") (pinfunction "Q3_5") (pintype "tri_state"))
    )
    (net (code "52") (name "/REG-IO2-DATA7") (class "Default")
      (node (ref "LED55") (pin "A") (pinfunction "A_A") (pintype "passive"))
      (node (ref "REG-IO2-BUF") (pin "9") (pinfunction "A8_9") (pintype "bidirectional"))
      (node (ref "REG-IO2-H") (pin "6") (pinfunction "Q4_6") (pintype "tri_state"))
    )
    (net (code "54") (name "/REG-IO3-DATA0") (class "Default")
      (node (ref "LED56") (pin "A") (pinfunction "A_A") (pintype "passive"))
      (node (ref "REG-IO3-BUF") (pin "2") (pinfunction "A1_2") (pintype "bidirectional"))
      (node (ref "REG-IO3-L") (pin "3") (pinfunction "Q1_3") (pintype "tri_state"))
    )
    (net (code "55") (name "/REG-IO3-DATA1") (class "Default")
      (node (ref "LED57") (pin "A") (pinfunction "A_A") (pintype "passive"))
      (node (ref "REG-IO3-BUF") (pin "3") (pinfunction "A2_3") (pintype "bidirectional"))
      (node (ref "REG-IO3-L") (pin "4") (pinfunction "Q2_4") (pintype "tri_state"))
    )
    (net (code "56") (name "/REG-IO3-DATA2") (class "Default")
      (node (ref "LED58") (pin "A") (pinfunction "A_A") (pintype "passive"))
      (node (ref "REG-IO3-BUF") (pin "4") (pinfunction "A3_4") (pintype "bidirectional"))
      (node (ref "REG-IO3-L") (pin "5") (pinfunction "Q3_5") (pintype "tri_state"))
    )
    (net (code "57") (name "/REG-IO3-DATA3") (class "Default")
      (node (ref "LED59") (pin "A") (pinfunction "A_A") (pintype "passive"))
      (node (ref "REG-IO3-BUF") (pin "5") (pinfunction "A4_5") (pintype "bidirectional"))
      (node (ref "REG-IO3-L") (pin "6") (pinfunction "Q4_6") (pintype "tri_state"))
    )
    (net (code "58") (name "/REG-IO3-DATA4") (class "Default")
      (node (ref "LED60") (pin "A") (pinfunction "A_A") (pintype "passive"))
      (node (ref "REG-IO3-BUF") (pin "6") (pinfunction "A5_6") (pintype "bidirectional"))
      (node (ref "REG-IO3-H") (pin "3") (pinfunction "Q1_3") (pintype "tri_state"))
    )
    (net (code "59") (name "/REG-IO3-DATA5") (class "Default")
      (node (ref "LED61") (pin "A") (pinfunction "A_A") (pintype "passive"))
      (node (ref "REG-IO3-BUF") (pin "7") (pinfunction "A6_7") (pintype "bidirectional"))
      (node (ref "REG-IO3-H") (pin "4") (pinfunction "Q2_4") (pintype "tri_state"))
    )
    (net (code "60") (name "/REG-IO3-DATA6") (class "Default")
      (node (ref "LED62") (pin "A") (pinfunction "A_A") (pintype "passive"))
      (node (ref "REG-IO3-BUF") (pin "8") (pinfunction "A7_8") (pintype "bidirectional"))
      (node (ref "REG-IO3-H") (pin "5") (pinfunction "Q3_5") (pintype "tri_state"))
    )
    (net (code "61") (name "/REG-IO3-DATA7") (class "Default")
      (node (ref "LED63") (pin "A") (pinfunction "A_A") (pintype "passive"))
      (node (ref "REG-IO3-BUF") (pin "9") (pinfunction "A8_9") (pintype "bidirectional"))
      (node (ref "REG-IO3-H") (pin "6") (pinfunction "Q4_6") (pintype "tri_state"))
    )
    (net (code "63") (name "/REG-IR-DATA0") (class "Default")
      (node (ref "LED24") (pin "A") (pinfunction "A_A") (pintype "passive"))
      (node (ref "REG-IR-BUF") (pin "2") (pinfunction "A1_2") (pintype "bidirectional"))
      (node (ref "REG-IR-L") (pin "3") (pinfunction "Q1_3") (pintype "tri_state"))
    )
    (net (code "64") (name "/REG-IR-DATA1") (class "Default")
      (node (ref "LED25") (pin "A") (pinfunction "A_A") (pintype "passive"))
      (node (ref "REG-IR-BUF") (pin "3") (pinfunction "A2_3") (pintype "bidirectional"))
      (node (ref "REG-IR-L") (pin "4") (pinfunction "Q2_4") (pintype "tri_state"))
    )
    (net (code "65") (name "/REG-IR-DATA2") (class "Default")
      (node (ref "LED26") (pin "A") (pinfunction "A_A") (pintype "passive"))
      (node (ref "REG-IR-BUF") (pin "4") (pinfunction "A3_4") (pintype "bidirectional"))
      (node (ref "REG-IR-L") (pin "5") (pinfunction "Q3_5") (pintype "tri_state"))
    )
    (net (code "66") (name "/REG-IR-DATA3") (class "Default")
      (node (ref "LED27") (pin "A") (pinfunction "A_A") (pintype "passive"))
      (node (ref "REG-IR-BUF") (pin "5") (pinfunction "A4_5") (pintype "bidirectional"))
      (node (ref "REG-IR-L") (pin "6") (pinfunction "Q4_6") (pintype "tri_state"))
    )
    (net (code "67") (name "/REG-IR-DATA4") (class "Default")
      (node (ref "LED28") (pin "A") (pinfunction "A_A") (pintype "passive"))
      (node (ref "REG-IR-BUF") (pin "6") (pinfunction "A5_6") (pintype "bidirectional"))
      (node (ref "REG-IR-H") (pin "3") (pinfunction "Q1_3") (pintype "tri_state"))
    )
    (net (code "68") (name "/REG-IR-DATA5") (class "Default")
      (node (ref "LED29") (pin "A") (pinfunction "A_A") (pintype "passive"))
      (node (ref "REG-IR-BUF") (pin "7") (pinfunction "A6_7") (pintype "bidirectional"))
      (node (ref "REG-IR-H") (pin "4") (pinfunction "Q2_4") (pintype "tri_state"))
    )
    (net (code "69") (name "/REG-IR-DATA6") (class "Default")
      (node (ref "LED30") (pin "A") (pinfunction "A_A") (pintype "passive"))
      (node (ref "REG-IR-BUF") (pin "8") (pinfunction "A7_8") (pintype "bidirectional"))
      (node (ref "REG-IR-H") (pin "5") (pinfunction "Q3_5") (pintype "tri_state"))
    )
    (net (code "70") (name "/REG-IR-DATA7") (class "Default")
      (node (ref "LED31") (pin "A") (pinfunction "A_A") (pintype "passive"))
      (node (ref "REG-IR-BUF") (pin "9") (pinfunction "A8_9") (pintype "bidirectional"))
      (node (ref "REG-IR-H") (pin "6") (pinfunction "Q4_6") (pintype "tri_state"))
    )
    (net (code "72") (name "/REG-MAR-DATA0") (class "Default")
      (node (ref "LED16") (pin "A") (pinfunction "A_A") (pintype "passive"))
      (node (ref "REG-MAR-BUF") (pin "2") (pinfunction "A1_2") (pintype "bidirectional"))
      (node (ref "REG-MAR-L") (pin "3") (pinfunction "Q1_3") (pintype "tri_state"))
    )
    (net (code "73") (name "/REG-MAR-DATA1") (class "Default")
      (node (ref "LED17") (pin "A") (pinfunction "A_A") (pintype "passive"))
      (node (ref "REG-MAR-BUF") (pin "3") (pinfunction "A2_3") (pintype "bidirectional"))
      (node (ref "REG-MAR-L") (pin "4") (pinfunction "Q2_4") (pintype "tri_state"))
    )
    (net (code "74") (name "/REG-MAR-DATA2") (class "Default")
      (node (ref "LED18") (pin "A") (pinfunction "A_A") (pintype "passive"))
      (node (ref "REG-MAR-BUF") (pin "4") (pinfunction "A3_4") (pintype "bidirectional"))
      (node (ref "REG-MAR-L") (pin "5") (pinfunction "Q3_5") (pintype "tri_state"))
    )
    (net (code "75") (name "/REG-MAR-DATA3") (class "Default")
      (node (ref "LED19") (pin "A") (pinfunction "A_A") (pintype "passive"))
      (node (ref "REG-MAR-BUF") (pin "5") (pinfunction "A4_5") (pintype "bidirectional"))
      (node (ref "REG-MAR-L") (pin "6") (pinfunction "Q4_6") (pintype "tri_state"))
    )
    (net (code "76") (name "/REG-MAR-DATA4") (class "Default")
      (node (ref "LED20") (pin "A") (pinfunction "A_A") (pintype "passive"))
      (node (ref "REG-MAR-BUF") (pin "6") (pinfunction "A5_6") (pintype "bidirectional"))
      (node (ref "REG-MAR-H") (pin "3") (pinfunction "Q1_3") (pintype "tri_state"))
    )
    (net (code "77") (name "/REG-MAR-DATA5") (class "Default")
      (node (ref "LED21") (pin "A") (pinfunction "A_A") (pintype "passive"))
      (node (ref "REG-MAR-BUF") (pin "7") (pinfunction "A6_7") (pintype "bidirectional"))
      (node (ref "REG-MAR-H") (pin "4") (pinfunction "Q2_4") (pintype "tri_state"))
    )
    (net (code "78") (name "/REG-MAR-DATA6") (class "Default")
      (node (ref "LED22") (pin "A") (pinfunction "A_A") (pintype "passive"))
      (node (ref "REG-MAR-BUF") (pin "8") (pinfunction "A7_8") (pintype "bidirectional"))
      (node (ref "REG-MAR-H") (pin "5") (pinfunction "Q3_5") (pintype "tri_state"))
    )
    (net (code "79") (name "/REG-MAR-DATA7") (class "Default")
      (node (ref "LED23") (pin "A") (pinfunction "A_A") (pintype "passive"))
      (node (ref "REG-MAR-BUF") (pin "9") (pinfunction "A8_9") (pintype "bidirectional"))
      (node (ref "REG-MAR-H") (pin "6") (pinfunction "Q4_6") (pintype "tri_state"))
    )
    (net (code "81") (name "/REG-MBR-DATA0") (class "Default")
      (node (ref "LED8") (pin "A") (pinfunction "A_A") (pintype "passive"))
      (node (ref "REG-MBR-BUF") (pin "2") (pinfunction "A1_2") (pintype "bidirectional"))
      (node (ref "REG-MBR-L") (pin "3") (pinfunction "Q1_3") (pintype "tri_state"))
    )
    (net (code "82") (name "/REG-MBR-DATA1") (class "Default")
      (node (ref "LED9") (pin "A") (pinfunction "A_A") (pintype "passive"))
      (node (ref "REG-MBR-BUF") (pin "3") (pinfunction "A2_3") (pintype "bidirectional"))
      (node (ref "REG-MBR-L") (pin "4") (pinfunction "Q2_4") (pintype "tri_state"))
    )
    (net (code "83") (name "/REG-MBR-DATA2") (class "Default")
      (node (ref "LED10") (pin "A") (pinfunction "A_A") (pintype "passive"))
      (node (ref "REG-MBR-BUF") (pin "4") (pinfunction "A3_4") (pintype "bidirectional"))
      (node (ref "REG-MBR-L") (pin "5") (pinfunction "Q3_5") (pintype "tri_state"))
    )
    (net (code "84") (name "/REG-MBR-DATA3") (class "Default")
      (node (ref "LED11") (pin "A") (pinfunction "A_A") (pintype "passive"))
      (node (ref "REG-MBR-BUF") (pin "5") (pinfunction "A4_5") (pintype "bidirectional"))
      (node (ref "REG-MBR-L") (pin "6") (pinfunction "Q4_6") (pintype "tri_state"))
    )
    (net (code "85") (name "/REG-MBR-DATA4") (class "Default")
      (node (ref "LED12") (pin "A") (pinfunction "A_A") (pintype "passive"))
      (node (ref "REG-MBR-BUF") (pin "6") (pinfunction "A5_6") (pintype "bidirectional"))
      (node (ref "REG-MBR-H") (pin "3") (pinfunction "Q1_3") (pintype "tri_state"))
    )
    (net (code "86") (name "/REG-MBR-DATA5") (class "Default")
      (node (ref "LED13") (pin "A") (pinfunction "A_A") (pintype "passive"))
      (node (ref "REG-MBR-BUF") (pin "7") (pinfunction "A6_7") (pintype "bidirectional"))
      (node (ref "REG-MBR-H") (pin "4") (pinfunction "Q2_4") (pintype "tri_state"))
    )
    (net (code "87") (name "/REG-MBR-DATA6") (class "Default")
      (node (ref "LED14") (pin "A") (pinfunction "A_A") (pintype "passive"))
      (node (ref "REG-MBR-BUF") (pin "8") (pinfunction "A7_8") (pintype "bidirectional"))
      (node (ref "REG-MBR-H") (pin "5") (pinfunction "Q3_5") (pintype "tri_state"))
    )
    (net (code "88") (name "/REG-MBR-DATA7") (class "Default")
      (node (ref "LED15") (pin "A") (pinfunction "A_A") (pintype "passive"))
      (node (ref "REG-MBR-BUF") (pin "9") (pinfunction "A8_9") (pintype "bidirectional"))
      (node (ref "REG-MBR-H") (pin "6") (pinfunction "Q4_6") (pintype "tri_state"))
    )
    (net (code "90") (name "CLK-SIG") (class "Default")
      (node (ref "REG-ACU-H") (pin "7") (pinfunction "CLK_7") (pintype "input"))
      (node (ref "REG-ACU-L") (pin "7") (pinfunction "CLK_7") (pintype "input"))
      (node (ref "REG-IO0-H") (pin "7") (pinfunction "CLK_7") (pintype "input"))
      (node (ref "REG-IO0-L") (pin "7") (pinfunction "CLK_7") (pintype "input"))
      (node (ref "REG-IO1-H") (pin "7") (pinfunction "CLK_7") (pintype "input"))
      (node (ref "REG-IO1-L") (pin "7") (pinfunction "CLK_7") (pintype "input"))
      (node (ref "REG-IO2-H") (pin "7") (pinfunction "CLK_7") (pintype "input"))
      (node (ref "REG-IO2-L") (pin "7") (pinfunction "CLK_7") (pintype "input"))
      (node (ref "REG-IO3-H") (pin "7") (pinfunction "CLK_7") (pintype "input"))
      (node (ref "REG-IO3-L") (pin "7") (pinfunction "CLK_7") (pintype "input"))
      (node (ref "REG-IR-H") (pin "7") (pinfunction "CLK_7") (pintype "input"))
      (node (ref "REG-IR-L") (pin "7") (pinfunction "CLK_7") (pintype "input"))
      (node (ref "REG-MAR-H") (pin "7") (pinfunction "CLK_7") (pintype "input"))
      (node (ref "REG-MAR-L") (pin "7") (pinfunction "CLK_7") (pintype "input"))
      (node (ref "REG-MBR-H") (pin "7") (pinfunction "CLK_7") (pintype "input"))
      (node (ref "REG-MBR-L") (pin "7") (pinfunction "CLK_7") (pintype "input"))
    )
    (net (code "91") (name "DATA-IR0") (class "Default")
      (node (ref "REG-IR-BUF") (pin "14") (pinfunction "B5_14") (pintype "bidirectional"))
    )
    (net (code "92") (name "DATA-IR1") (class "Default")
      (node (ref "REG-IR-BUF") (pin "13") (pinfunction "B6_13") (pintype "bidirectional"))
    )
    (net (code "93") (name "DATA-IR2") (class "Default")
      (node (ref "REG-IR-BUF") (pin "12") (pinfunction "B7_12") (pintype "bidirectional"))
    )
    (net (code "94") (name "DATA-IR3") (class "Default")
      (node (ref "REG-IR-BUF") (pin "11") (pinfunction "B8_11") (pintype "bidirectional"))
    )
    (net (code "95") (name "GND") (class "Default")
      (node (ref "LED0") (pin "K") (pinfunction "C_K") (pintype "passive"))
      (node (ref "LED1") (pin "K") (pinfunction "C_K") (pintype "passive"))
      (node (ref "LED10") (pin "K") (pinfunction "C_K") (pintype "passive"))
      (node (ref "LED11") (pin "K") (pinfunction "C_K") (pintype "passive"))
      (node (ref "LED12") (pin "K") (pinfunction "C_K") (pintype "passive"))
      (node (ref "LED13") (pin "K") (pinfunction "C_K") (pintype "passive"))
      (node (ref "LED14") (pin "K") (pinfunction "C_K") (pintype "passive"))
      (node (ref "LED15") (pin "K") (pinfunction "C_K") (pintype "passive"))
      (node (ref "LED16") (pin "K") (pinfunction "C_K") (pintype "passive"))
      (node (ref "LED17") (pin "K") (pinfunction "C_K") (pintype "passive"))
      (node (ref "LED18") (pin "K") (pinfunction "C_K") (pintype "passive"))
      (node (ref "LED19") (pin "K") (pinfunction "C_K") (pintype "passive"))
      (node (ref "LED2") (pin "K") (pinfunction "C_K") (pintype "passive"))
      (node (ref "LED20") (pin "K") (pinfunction "C_K") (pintype "passive"))
      (node (ref "LED21") (pin "K") (pinfunction "C_K") (pintype "passive"))
      (node (ref "LED22") (pin "K") (pinfunction "C_K") (pintype "passive"))
      (node (ref "LED23") (pin "K") (pinfunction "C_K") (pintype "passive"))
      (node (ref "LED24") (pin "K") (pinfunction "C_K") (pintype "passive"))
      (node (ref "LED25") (pin "K") (pinfunction "C_K") (pintype "passive"))
      (node (ref "LED26") (pin "K") (pinfunction "C_K") (pintype "passive"))
      (node (ref "LED27") (pin "K") (pinfunction "C_K") (pintype "passive"))
      (node (ref "LED28") (pin "K") (pinfunction "C_K") (pintype "passive"))
      (node (ref "LED29") (pin "K") (pinfunction "C_K") (pintype "passive"))
      (node (ref "LED3") (pin "K") (pinfunction "C_K") (pintype "passive"))
      (node (ref "LED30") (pin "K") (pinfunction "C_K") (pintype "passive"))
      (node (ref "LED31") (pin "K") (pinfunction "C_K") (pintype "passive"))
      (node (ref "LED32") (pin "K") (pinfunction "C_K") (pintype "passive"))
      (node (ref "LED33") (pin "K") (pinfunction "C_K") (pintype "passive"))
      (node (ref "LED34") (pin "K") (pinfunction "C_K") (pintype "passive"))
      (node (ref "LED35") (pin "K") (pinfunction "C_K") (pintype "passive"))
      (node (ref "LED36") (pin "K") (pinfunction "C_K") (pintype "passive"))
      (node (ref "LED37") (pin "K") (pinfunction "C_K") (pintype "passive"))
      (node (ref "LED38") (pin "K") (pinfunction "C_K") (pintype "passive"))
      (node (ref "LED39") (pin "K") (pinfunction "C_K") (pintype "passive"))
      (node (ref "LED4") (pin "K") (pinfunction "C_K") (pintype "passive"))
      (node (ref "LED40") (pin "K") (pinfunction "C_K") (pintype "passive"))
      (node (ref "LED41") (pin "K") (pinfunction "C_K") (pintype "passive"))
      (node (ref "LED42") (pin "K") (pinfunction "C_K") (pintype "passive"))
      (node (ref "LED43") (pin "K") (pinfunction "C_K") (pintype "passive"))
      (node (ref "LED44") (pin "K") (pinfunction "C_K") (pintype "passive"))
      (node (ref "LED45") (pin "K") (pinfunction "C_K") (pintype "passive"))
      (node (ref "LED46") (pin "K") (pinfunction "C_K") (pintype "passive"))
      (node (ref "LED47") (pin "K") (pinfunction "C_K") (pintype "passive"))
      (node (ref "LED48") (pin "K") (pinfunction "C_K") (pintype "passive"))
      (node (ref "LED49") (pin "K") (pinfunction "C_K") (pintype "passive"))
      (node (ref "LED5") (pin "K") (pinfunction "C_K") (pintype "passive"))
      (node (ref "LED50") (pin "K") (pinfunction "C_K") (pintype "passive"))
      (node (ref "LED51") (pin "K") (pinfunction "C_K") (pintype "passive"))
      (node (ref "LED52") (pin "K") (pinfunction "C_K") (pintype "passive"))
      (node (ref "LED53") (pin "K") (pinfunction "C_K") (pintype "passive"))
      (node (ref "LED54") (pin "K") (pinfunction "C_K") (pintype "passive"))
      (node (ref "LED55") (pin "K") (pinfunction "C_K") (pintype "passive"))
      (node (ref "LED56") (pin "K") (pinfunction "C_K") (pintype "passive"))
      (node (ref "LED57") (pin "K") (pinfunction "C_K") (pintype "passive"))
      (node (ref "LED58") (pin "K") (pinfunction "C_K") (pintype "passive"))
      (node (ref "LED59") (pin "K") (pinfunction "C_K") (pintype "passive"))
      (node (ref "LED6") (pin "K") (pinfunction "C_K") (pintype "passive"))
      (node (ref "LED60") (pin "K") (pinfunction "C_K") (pintype "passive"))
      (node (ref "LED61") (pin "K") (pinfunction "C_K") (pintype "passive"))
      (node (ref "LED62") (pin "K") (pinfunction "C_K") (pintype "passive"))
      (node (ref "LED63") (pin "K") (pinfunction "C_K") (pintype "passive"))
      (node (ref "LED7") (pin "K") (pinfunction "C_K") (pintype "passive"))
      (node (ref "LED8") (pin "K") (pinfunction "C_K") (pintype "passive"))
      (node (ref "LED9") (pin "K") (pinfunction "C_K") (pintype "passive"))
      (node (ref "REG-ACU-H") (pin "1") (pinfunction "M_1") (pintype "input"))
      (node (ref "REG-ACU-H") (pin "15") (pinfunction "CLR_15") (pintype "input"))
      (node (ref "REG-ACU-H") (pin "2") (pinfunction "N_2") (pintype "input"))
      (node (ref "REG-ACU-L") (pin "1") (pinfunction "M_1") (pintype "input"))
      (node (ref "REG-ACU-L") (pin "15") (pinfunction "CLR_15") (pintype "input"))
      (node (ref "REG-ACU-L") (pin "2") (pinfunction "N_2") (pintype "input"))
      (node (ref "REG-IO0-H") (pin "1") (pinfunction "M_1") (pintype "input"))
      (node (ref "REG-IO0-H") (pin "15") (pinfunction "CLR_15") (pintype "input"))
      (node (ref "REG-IO0-H") (pin "2") (pinfunction "N_2") (pintype "input"))
      (node (ref "REG-IO0-L") (pin "1") (pinfunction "M_1") (pintype "input"))
      (node (ref "REG-IO0-L") (pin "15") (pinfunction "CLR_15") (pintype "input"))
      (node (ref "REG-IO0-L") (pin "2") (pinfunction "N_2") (pintype "input"))
      (node (ref "REG-IO1-H") (pin "1") (pinfunction "M_1") (pintype "input"))
      (node (ref "REG-IO1-H") (pin "15") (pinfunction "CLR_15") (pintype "input"))
      (node (ref "REG-IO1-H") (pin "2") (pinfunction "N_2") (pintype "input"))
      (node (ref "REG-IO1-L") (pin "1") (pinfunction "M_1") (pintype "input"))
      (node (ref "REG-IO1-L") (pin "15") (pinfunction "CLR_15") (pintype "input"))
      (node (ref "REG-IO1-L") (pin "2") (pinfunction "N_2") (pintype "input"))
      (node (ref "REG-IO2-H") (pin "1") (pinfunction "M_1") (pintype "input"))
      (node (ref "REG-IO2-H") (pin "15") (pinfunction "CLR_15") (pintype "input"))
      (node (ref "REG-IO2-H") (pin "2") (pinfunction "N_2") (pintype "input"))
      (node (ref "REG-IO2-L") (pin "1") (pinfunction "M_1") (pintype "input"))
      (node (ref "REG-IO2-L") (pin "15") (pinfunction "CLR_15") (pintype "input"))
      (node (ref "REG-IO2-L") (pin "2") (pinfunction "N_2") (pintype "input"))
      (node (ref "REG-IO3-H") (pin "1") (pinfunction "M_1") (pintype "input"))
      (node (ref "REG-IO3-H") (pin "15") (pinfunction "CLR_15") (pintype "input"))
      (node (ref "REG-IO3-H") (pin "2") (pinfunction "N_2") (pintype "input"))
      (node (ref "REG-IO3-L") (pin "1") (pinfunction "M_1") (pintype "input"))
      (node (ref "REG-IO3-L") (pin "15") (pinfunction "CLR_15") (pintype "input"))
      (node (ref "REG-IO3-L") (pin "2") (pinfunction "N_2") (pintype "input"))
      (node (ref "REG-IR-H") (pin "1") (pinfunction "M_1") (pintype "input"))
      (node (ref "REG-IR-H") (pin "15") (pinfunction "CLR_15") (pintype "input"))
      (node (ref "REG-IR-H") (pin "2") (pinfunction "N_2") (pintype "input"))
      (node (ref "REG-IR-L") (pin "1") (pinfunction "M_1") (pintype "input"))
      (node (ref "REG-IR-L") (pin "15") (pinfunction "CLR_15") (pintype "input"))
      (node (ref "REG-IR-L") (pin "2") (pinfunction "N_2") (pintype "input"))
      (node (ref "REG-MAR-H") (pin "1") (pinfunction "M_1") (pintype "input"))
      (node (ref "REG-MAR-H") (pin "15") (pinfunction "CLR_15") (pintype "input"))
      (node (ref "REG-MAR-H") (pin "2") (pinfunction "N_2") (pintype "input"))
      (node (ref "REG-MAR-L") (pin "1") (pinfunction "M_1") (pintype "input"))
      (node (ref "REG-MAR-L") (pin "15") (pinfunction "CLR_15") (pintype "input"))
      (node (ref "REG-MAR-L") (pin "2") (pinfunction "N_2") (pintype "input"))
      (node (ref "REG-MBR-H") (pin "1") (pinfunction "M_1") (pintype "input"))
      (node (ref "REG-MBR-H") (pin "15") (pinfunction "CLR_15") (pintype "input"))
      (node (ref "REG-MBR-H") (pin "2") (pinfunction "N_2") (pintype "input"))
      (node (ref "REG-MBR-L") (pin "1") (pinfunction "M_1") (pintype "input"))
      (node (ref "REG-MBR-L") (pin "15") (pinfunction "CLR_15") (pintype "input"))
      (node (ref "REG-MBR-L") (pin "2") (pinfunction "N_2") (pintype "input"))
    )
    (net (code "96") (name "REG-ACU-LOAD-IN") (class "Default")
      (node (ref "REG-ACU-H") (pin "10") (pinfunction "G2_10") (pintype "input"))
      (node (ref "REG-ACU-H") (pin "9") (pinfunction "G1_9") (pintype "input"))
      (node (ref "REG-ACU-L") (pin "10") (pinfunction "G2_10") (pintype "input"))
      (node (ref "REG-ACU-L") (pin "9") (pinfunction "G1_9") (pintype "input"))
    )
    (net (code "97") (name "REG-IO0-LOAD-IN") (class "Default")
      (node (ref "REG-IO0-H") (pin "10") (pinfunction "G2_10") (pintype "input"))
      (node (ref "REG-IO0-H") (pin "9") (pinfunction "G1_9") (pintype "input"))
      (node (ref "REG-IO0-L") (pin "10") (pinfunction "G2_10") (pintype "input"))
      (node (ref "REG-IO0-L") (pin "9") (pinfunction "G1_9") (pintype "input"))
    )
    (net (code "98") (name "REG-IO0-LOAD-OUT") (class "Default")
      (node (ref "REG-IO0-BUF") (pin "19") (pinfunction "G_19") (pintype "input"))
    )
    (net (code "99") (name "REG-IO1-LOAD-IN") (class "Default")
      (node (ref "REG-IO1-H") (pin "10") (pinfunction "G2_10") (pintype "input"))
      (node (ref "REG-IO1-H") (pin "9") (pinfunction "G1_9") (pintype "input"))
      (node (ref "REG-IO1-L") (pin "10") (pinfunction "G2_10") (pintype "input"))
      (node (ref "REG-IO1-L") (pin "9") (pinfunction "G1_9") (pintype "input"))
    )
    (net (code "100") (name "REG-IO1-LOAD-OUT") (class "Default")
      (node (ref "REG-IO1-BUF") (pin "19") (pinfunction "G_19") (pintype "input"))
    )
    (net (code "101") (name "REG-IO2-LOAD-IN") (class "Default")
      (node (ref "REG-IO2-H") (pin "10") (pinfunction "G2_10") (pintype "input"))
      (node (ref "REG-IO2-H") (pin "9") (pinfunction "G1_9") (pintype "input"))
      (node (ref "REG-IO2-L") (pin "10") (pinfunction "G2_10") (pintype "input"))
      (node (ref "REG-IO2-L") (pin "9") (pinfunction "G1_9") (pintype "input"))
    )
    (net (code "102") (name "REG-IO2-LOAD-OUT") (class "Default")
      (node (ref "REG-IO2-BUF") (pin "19") (pinfunction "G_19") (pintype "input"))
    )
    (net (code "103") (name "REG-IO3-LOAD-IN") (class "Default")
      (node (ref "REG-IO3-H") (pin "10") (pinfunction "G2_10") (pintype "input"))
      (node (ref "REG-IO3-H") (pin "9") (pinfunction "G1_9") (pintype "input"))
      (node (ref "REG-IO3-L") (pin "10") (pinfunction "G2_10") (pintype "input"))
      (node (ref "REG-IO3-L") (pin "9") (pinfunction "G1_9") (pintype "input"))
    )
    (net (code "104") (name "REG-IO3-LOAD-OUT") (class "Default")
      (node (ref "REG-IO3-BUF") (pin "19") (pinfunction "G_19") (pintype "input"))
    )
    (net (code "105") (name "REG-IR-LOAD-IN") (class "Default")
      (node (ref "REG-IR-H") (pin "10") (pinfunction "G2_10") (pintype "input"))
      (node (ref "REG-IR-H") (pin "9") (pinfunction "G1_9") (pintype "input"))
      (node (ref "REG-IR-L") (pin "10") (pinfunction "G2_10") (pintype "input"))
      (node (ref "REG-IR-L") (pin "9") (pinfunction "G1_9") (pintype "input"))
    )
    (net (code "106") (name "REG-IR-LOAD-OUT") (class "Default")
      (node (ref "REG-IR-BUF") (pin "19") (pinfunction "G_19") (pintype "input"))
    )
    (net (code "107") (name "REG-MAR-LOAD-IN") (class "Default")
      (node (ref "REG-MAR-H") (pin "10") (pinfunction "G2_10") (pintype "input"))
      (node (ref "REG-MAR-H") (pin "9") (pinfunction "G1_9") (pintype "input"))
      (node (ref "REG-MAR-L") (pin "10") (pinfunction "G2_10") (pintype "input"))
      (node (ref "REG-MAR-L") (pin "9") (pinfunction "G1_9") (pintype "input"))
    )
    (net (code "108") (name "REG-MAR-LOAD-OUT") (class "Default")
      (node (ref "REG-MAR-BUF") (pin "19") (pinfunction "G_19") (pintype "input"))
    )
    (net (code "109") (name "REG-MBR-LOAD-IN") (class "Default")
      (node (ref "REG-MBR-H") (pin "10") (pinfunction "G2_10") (pintype "input"))
      (node (ref "REG-MBR-H") (pin "9") (pinfunction "G1_9") (pintype "input"))
      (node (ref "REG-MBR-L") (pin "10") (pinfunction "G2_10") (pintype "input"))
      (node (ref "REG-MBR-L") (pin "9") (pinfunction "G1_9") (pintype "input"))
    )
    (net (code "110") (name "REG-MBR-LOAD-OUT") (class "Default")
      (node (ref "REG-MBR-BUF") (pin "19") (pinfunction "G_19") (pintype "input"))
    )
    (net (code "111") (name "REG-SC-LOAD-OUT") (class "Default")
      (node (ref "REG-ACU-BUF") (pin "19") (pinfunction "G_19") (pintype "input"))
    )
    (net (code "112") (name "VCC") (class "Default")
      (node (ref "REG-ACU-BUF") (pin "1") (pinfunction "DIR_1") (pintype "input"))
      (node (ref "REG-IO0-BUF") (pin "1") (pinfunction "DIR_1") (pintype "input"))
      (node (ref "REG-IO1-BUF") (pin "1") (pinfunction "DIR_1") (pintype "input"))
      (node (ref "REG-IO2-BUF") (pin "1") (pinfunction "DIR_1") (pintype "input"))
      (node (ref "REG-IO3-BUF") (pin "1") (pinfunction "DIR_1") (pintype "input"))
      (node (ref "REG-IR-BUF") (pin "1") (pinfunction "DIR_1") (pintype "input"))
      (node (ref "REG-MAR-BUF") (pin "1") (pinfunction "DIR_1") (pintype "input"))
      (node (ref "REG-MBR-BUF") (pin "1") (pinfunction "DIR_1") (pintype "input"))
    )
  )
)
